# Spindle_Control.net
KiCad netlist of a schematic drawn in Altium Designer
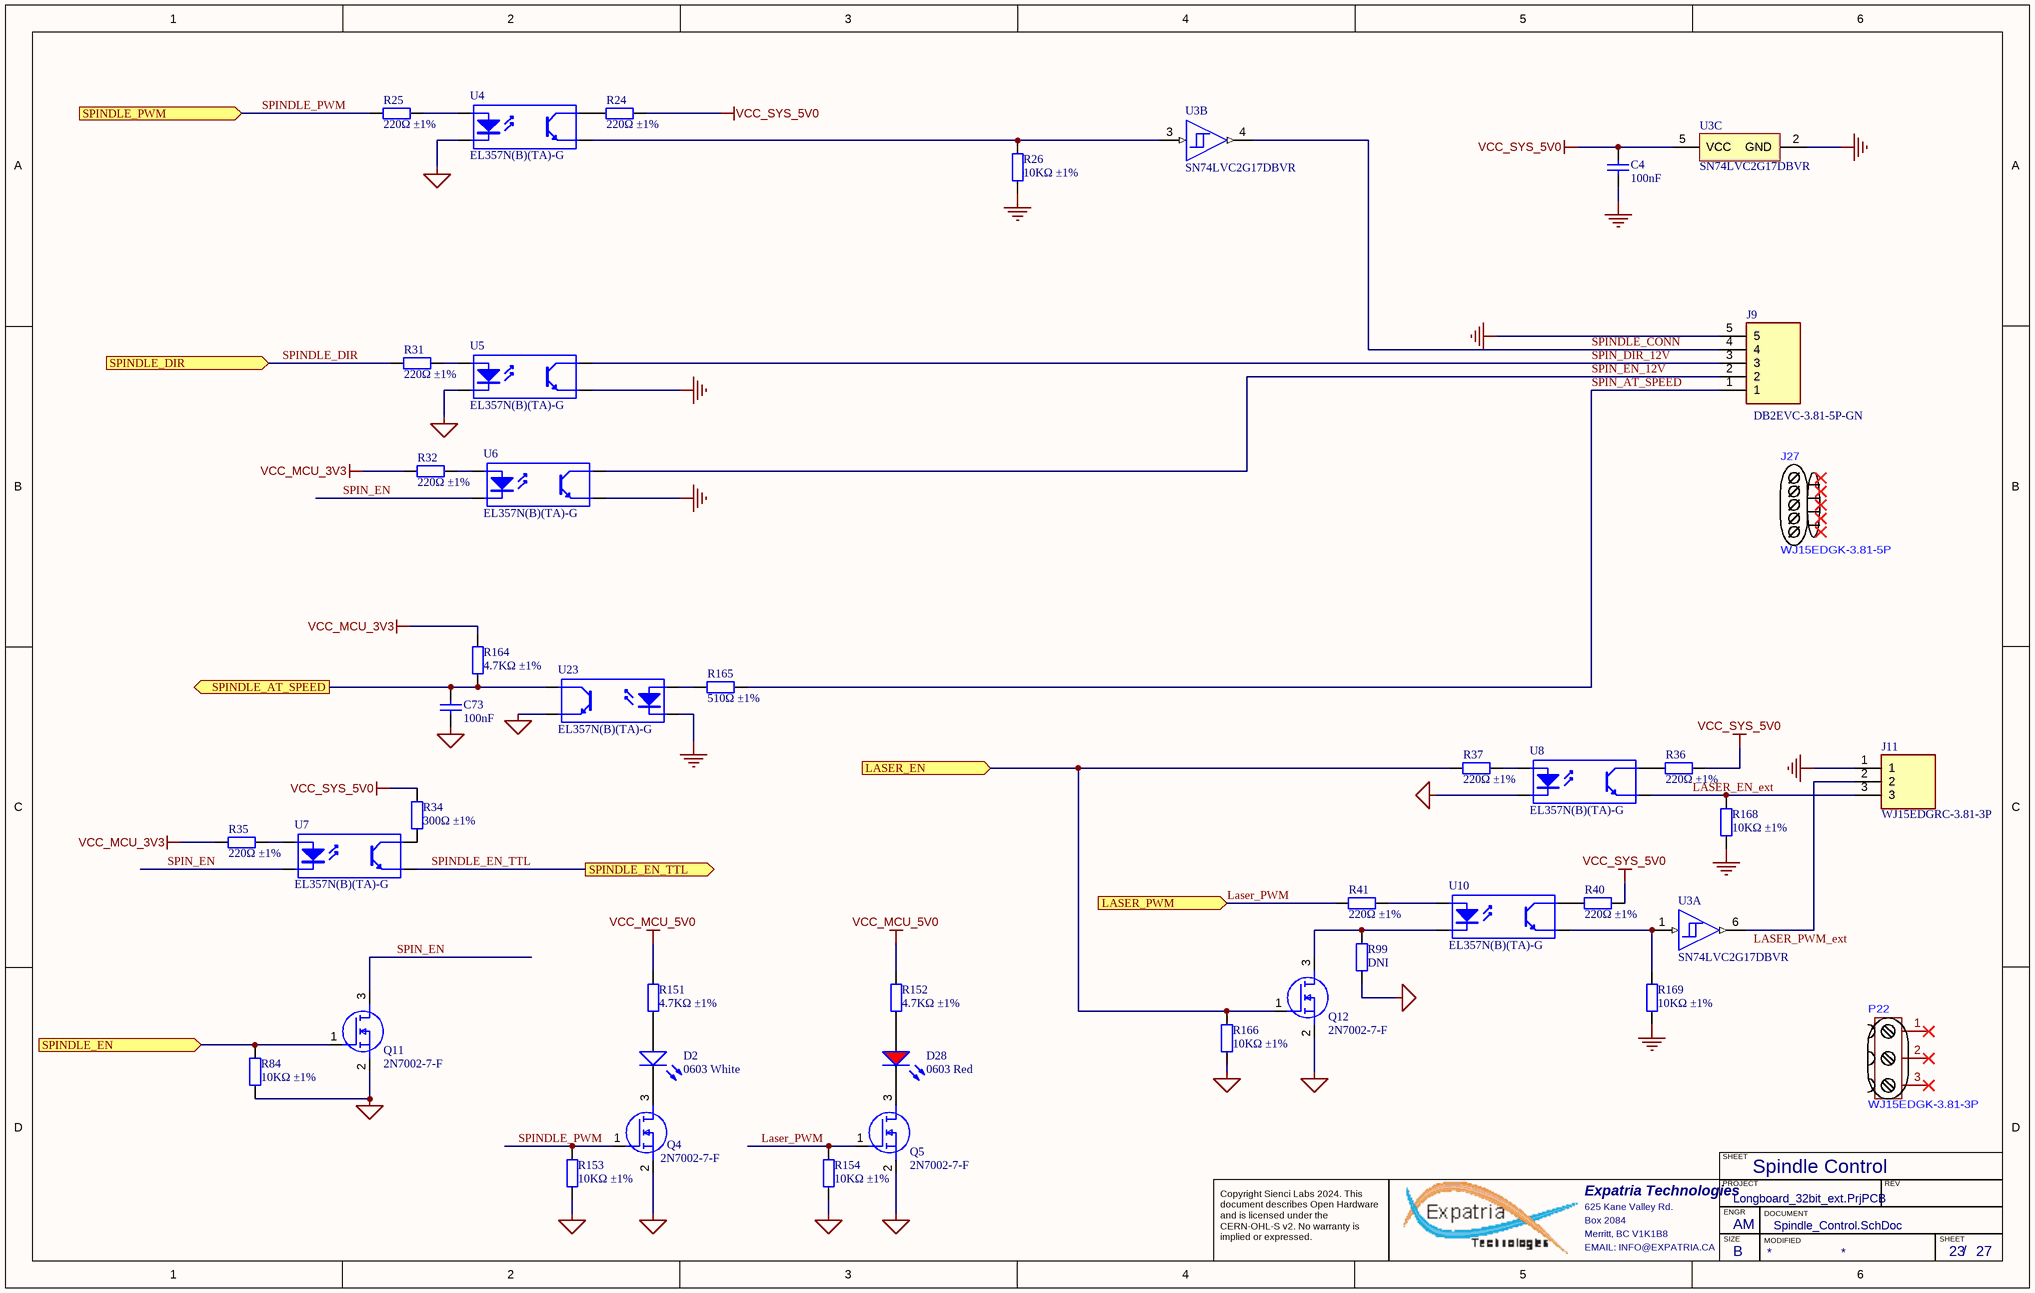
[diagram p0: Spindle_Control.SchDoc]

(export (version "E")
  (design (tool "Eeschema 10.0.6"))
  (components
    (comp (ref "C4")
      (value "100nF")
      (footprint "0603_C")
      (description "50V 100nF X7R ±10% 0603 Multilayer Ceramic Capacitors MLCC - SMD/SMT ROHS")
      (fields
        (field (name "MANUFACTURER") "YAGEO")
        (field (name "MANUFACTURER PART NUMBER") "CC0603KRX7R9BB104")
      )
      (libsource (lib "Sienci_Labs") (part "0603 100nF (104) 10% 50V"))
    )
    (comp (ref "C73")
      (value "100nF")
      (footprint "0402_C")
      (description "16V 100nF X7R ±10% 0402 Multilayer Ceramic Capacitors MLCC - SMD/SMT ROHS")
      (fields (field (name "MANUFACTURER") "Samsung Electro-Mechanics") (field (name "TOLERANCE") "10%"))
      (libsource (lib "Sienci_Labs") (part "0402 100nF (104) 10% 16V"))
    )
    (comp (ref "D2")
      (value "0603 White")
      (footprint "0603_LED_S1 - white")
      (description "White LED")
      (fields
        (field (name "MANUFACTURER PART NUMBER") "19-218/T1D-CQ2R2TY/3T")
        (field (name "MANUFACTURER") "Everlight Elec")
      )
      (libsource (lib "Sienci_Labs") (part "19-218/T1D-CQ2R2TY/3T"))
    )
    (comp (ref "D28")
      (value "0603 Red")
      (footprint "0603_LED_S1")
      (description "-40℃~+85℃ Red 0603 Light Emitting Diodes (LED) ROHS")
      (fields
        (field (name "MANUFACTURER") "Hubei KENTO Elec")
        (field (name "MANUFACTURER PART NUMBER") "KT-0603R")
      )
      (libsource (lib "Sienci_Labs") (part "KT-0603R"))
    )
    (comp (ref "J9")
      (value "DB2EVC-3.81-5P-GN")
      (footprint "CONN-TH_5P-P3.81_DB2EVC-3.81-5P")
      (description "3.81mm Green Board Edge/Receptacle-Close Push-Pull,P=3.81mm Pluggable System Terminal Block ROHS")
      (fields (field (name "MANUFACTURER") "DIBO"))
      (libsource (lib "Sienci_Labs") (part "DB2EVC-3.81-5P-GN"))
    )
    (comp (ref "J11")
      (value "WJ15EDGRC-3.81-3P")
      (footprint "SHDRRA3W85P0X381_1X3_1231X915X720P")
      (description "3.81mm Green Board Edge/Receptacle-Close Push-Pull,P=3.81mm Pluggable System Terminal Block ROHS")
      (fields (field (name "MANUFACTURER") "Ningbo Kangnex"))
      (libsource (lib "Sienci_Labs") (part "WJ15EDGRC-3.81-3P"))
    )
    (comp (ref "J27")
      (value "WJ15EDGK-3.81-5P")
      (description "3.81mm Green Plug P=3.81mm Pluggable System Terminal Block ROHS")
      (fields (field (name "MANUFACTURER") "Ningbo Kangnex Elec"))
      (libsource (lib "Sienci_Labs") (part "WJ15EDGK-3.81-5P"))
    )
    (comp (ref "P22")
      (value "WJ15EDGK-3.81-3P")
      (description "3.81mm Green Plug P=3.81mm Pluggable System Terminal Block ROHS")
      (fields (field (name "MANUFACTURER") "Ningbo"))
      (libsource (lib "Sienci_Labs") (part "WJ15EDGK-3.81-3P"))
    )
    (comp (ref "Q4")
      (value "2N7002-7-F")
      (footprint "SOT-23(SOT-23-3)")
      (description "60V 115mA 7.5Ω@5V,50mA 370mW N Channel SOT-23 MOSFETs ROHS")
      (fields (field (name "MANUFACTURER") "Diodes Inc.") (field (name "MOUSER PART NUMBER") "621-2N7002-F"))
      (libsource (lib "Sienci_Labs") (part "2N7002-7-F"))
    )
    (comp (ref "Q5")
      (value "2N7002-7-F")
      (footprint "SOT-23(SOT-23-3)")
      (description "60V 115mA 7.5Ω@5V,50mA 370mW N Channel SOT-23 MOSFETs ROHS")
      (fields (field (name "MANUFACTURER") "Diodes Inc.") (field (name "MOUSER PART NUMBER") "621-2N7002-F"))
      (libsource (lib "Sienci_Labs") (part "2N7002-7-F"))
    )
    (comp (ref "Q11")
      (value "2N7002-7-F")
      (footprint "SOT-23(SOT-23-3)")
      (description "60V 115mA 7.5Ω@5V,50mA 370mW N Channel SOT-23 MOSFETs ROHS")
      (fields (field (name "MANUFACTURER") "Diodes Inc.") (field (name "MOUSER PART NUMBER") "621-2N7002-F"))
      (libsource (lib "Sienci_Labs") (part "2N7002-7-F"))
    )
    (comp (ref "Q12")
      (value "2N7002-7-F")
      (footprint "SOT-23(SOT-23-3)")
      (description "60V 115mA 7.5Ω@5V,50mA 370mW N Channel SOT-23 MOSFETs ROHS")
      (fields (field (name "MANUFACTURER") "Diodes Inc.") (field (name "MOUSER PART NUMBER") "621-2N7002-F"))
      (libsource (lib "Sienci_Labs") (part "2N7002-7-F"))
    )
    (comp (ref "R24")
      (value "220Ω ±1%")
      (footprint "0402_R")
      (description "Chip resistor")
      (fields
        (field (name "MANUFACTURER") "Uniroyal Elec")
        (field (name "MANUFACTURER PART NUMBER") "0402WGF2200TCE")
      )
      (libsource (lib "RES") (part "0402 220R (2200) 1%"))
    )
    (comp (ref "R25")
      (value "220Ω ±1%")
      (footprint "0402_R")
      (description "Chip resistor")
      (fields
        (field (name "MANUFACTURER") "Uniroyal Elec")
        (field (name "MANUFACTURER PART NUMBER") "0402WGF2200TCE")
      )
      (libsource (lib "RES") (part "0402 220R (2200) 1%"))
    )
    (comp (ref "R26")
      (value "10KΩ ±1%")
      (footprint "0402_R")
      (description "Chip resistor")
      (fields
        (field (name "MANUFACTURER") "Uniroyal Elec")
        (field (name "MANUFACTURER PART NUMBER") "0402WGF1002TCE")
      )
      (libsource (lib "Sienci_Labs") (part "0402 10K (1002) 1%"))
    )
    (comp (ref "R31")
      (value "220Ω ±1%")
      (footprint "0402_R")
      (description "Chip resistor")
      (fields
        (field (name "MANUFACTURER") "Uniroyal Elec")
        (field (name "MANUFACTURER PART NUMBER") "0402WGF2200TCE")
      )
      (libsource (lib "RES") (part "0402 220R (2200) 1%"))
    )
    (comp (ref "R32")
      (value "220Ω ±1%")
      (footprint "0402_R")
      (description "Chip resistor")
      (fields
        (field (name "MANUFACTURER") "Uniroyal Elec")
        (field (name "MANUFACTURER PART NUMBER") "0402WGF2200TCE")
      )
      (libsource (lib "RES") (part "0402 220R (2200) 1%"))
    )
    (comp (ref "R34")
      (value "300Ω ±1%")
      (footprint "0603_R")
      (description "Chip resistor")
      (fields
        (field (name "MANUFACTURER") "Uniroyal Elec")
        (field (name "MANUFACTURER PART NUMBER") "0603WAF3000T5E")
      )
      (libsource (lib "RES") (part "0603 300R (3000) 1%"))
    )
    (comp (ref "R35")
      (value "220Ω ±1%")
      (footprint "0402_R")
      (description "Chip resistor")
      (fields
        (field (name "MANUFACTURER") "Uniroyal Elec")
        (field (name "MANUFACTURER PART NUMBER") "0402WGF2200TCE")
      )
      (libsource (lib "RES") (part "0402 220R (2200) 1%"))
    )
    (comp (ref "R36")
      (value "220Ω ±1%")
      (footprint "0402_R")
      (description "Chip resistor")
      (fields
        (field (name "MANUFACTURER") "Uniroyal Elec")
        (field (name "MANUFACTURER PART NUMBER") "0402WGF2200TCE")
      )
      (libsource (lib "RES") (part "0402 220R (2200) 1%"))
    )
    (comp (ref "R37")
      (value "220Ω ±1%")
      (footprint "0402_R")
      (description "Chip resistor")
      (fields
        (field (name "MANUFACTURER") "Uniroyal Elec")
        (field (name "MANUFACTURER PART NUMBER") "0402WGF2200TCE")
      )
      (libsource (lib "RES") (part "0402 220R (2200) 1%"))
    )
    (comp (ref "R40")
      (value "220Ω ±1%")
      (footprint "0402_R")
      (description "Chip resistor")
      (fields
        (field (name "MANUFACTURER") "Uniroyal Elec")
        (field (name "MANUFACTURER PART NUMBER") "0402WGF2200TCE")
      )
      (libsource (lib "") (part "0402 220R (2200) 1%_1"))
    )
    (comp (ref "R41")
      (value "220Ω ±1%")
      (footprint "0402_R")
      (description "Chip resistor")
      (fields
        (field (name "MANUFACTURER") "Uniroyal Elec")
        (field (name "MANUFACTURER PART NUMBER") "0402WGF2200TCE")
      )
      (libsource (lib "RES") (part "0402 220R (2200) 1%"))
    )
    (comp (ref "R84")
      (value "10KΩ ±1%")
      (footprint "0402_R")
      (description "Chip resistor")
      (fields
        (field (name "MANUFACTURER") "Uniroyal Elec")
        (field (name "MANUFACTURER PART NUMBER") "0402WGF1002TCE")
      )
      (libsource (lib "Sienci_Labs") (part "0402 10K (1002) 1%"))
    )
    (comp (ref "R99")
      (value "DNI")
      (footprint "0603_R")
      (description "Chip resistor")
      (fields
        (field (name "MANUFACTURER") "Uniroyal Elec")
        (field (name "MANUFACTURER PART NUMBER") "0603WAF0000T5E")
      )
      (libsource (lib "Sienci_Labs") (part "0603 0R (0R0) 1%"))
    )
    (comp (ref "R151")
      (value "4.7KΩ ±1%")
      (footprint "0402_R")
      (description "Chip resistor")
      (fields
        (field (name "MANUFACTURER") "Uniroyal Elec")
        (field (name "MANUFACTURER PART NUMBER") "0402WGF4701TCE")
      )
      (libsource (lib "Sienci_Labs") (part "0402 4.7K (4701) 1%"))
    )
    (comp (ref "R152")
      (value "4.7KΩ ±1%")
      (footprint "0402_R")
      (description "Chip resistor")
      (fields
        (field (name "MANUFACTURER") "Uniroyal Elec")
        (field (name "MANUFACTURER PART NUMBER") "0402WGF4701TCE")
      )
      (libsource (lib "Sienci_Labs") (part "0402 4.7K (4701) 1%"))
    )
    (comp (ref "R153")
      (value "10KΩ ±1%")
      (footprint "0402_R")
      (description "Chip resistor")
      (fields
        (field (name "MANUFACTURER") "Uniroyal Elec")
        (field (name "MANUFACTURER PART NUMBER") "0402WGF1002TCE")
      )
      (libsource (lib "Sienci_Labs") (part "0402 10K (1002) 1%"))
    )
    (comp (ref "R154")
      (value "10KΩ ±1%")
      (footprint "0402_R")
      (description "Chip resistor")
      (fields
        (field (name "MANUFACTURER") "Uniroyal Elec")
        (field (name "MANUFACTURER PART NUMBER") "0402WGF1002TCE")
      )
      (libsource (lib "Sienci_Labs") (part "0402 10K (1002) 1%"))
    )
    (comp (ref "R164")
      (value "4.7KΩ ±1%")
      (footprint "0402_R")
      (description "Chip resistor")
      (fields (field (name "MANUFACTURER") "Uniroyal Elec") (field (name "POWER") "1/16W"))
      (libsource (lib "") (part "0402 4.7K (4701) 1%_1"))
    )
    (comp (ref "R165")
      (value "510Ω ±1%")
      (footprint "0402_R")
      (description "Chip resistor")
      (fields
        (field (name "MANUFACTURER") "Uniroyal Elec")
        (field (name "MANUFACTURER PART NUMBER") "0402WGF5100TCE")
      )
      (libsource (lib "RES") (part "0402 510R (5100) 1%"))
    )
    (comp (ref "R166")
      (value "10KΩ ±1%")
      (footprint "0402_R")
      (description "Chip resistor")
      (fields
        (field (name "MANUFACTURER") "Uniroyal Elec")
        (field (name "MANUFACTURER PART NUMBER") "0402WGF1002TCE")
      )
      (libsource (lib "Sienci_Labs") (part "0402 10K (1002) 1%"))
    )
    (comp (ref "R168")
      (value "10KΩ ±1%")
      (footprint "0402_R")
      (description "Chip resistor")
      (fields
        (field (name "MANUFACTURER") "Uniroyal Elec")
        (field (name "MANUFACTURER PART NUMBER") "0402WGF1002TCE")
      )
      (libsource (lib "Sienci_Labs") (part "0402 10K (1002) 1%"))
    )
    (comp (ref "R169")
      (value "10KΩ ±1%")
      (footprint "0402_R")
      (description "Chip resistor")
      (fields
        (field (name "MANUFACTURER") "Uniroyal Elec")
        (field (name "MANUFACTURER PART NUMBER") "0402WGF1002TCE")
      )
      (libsource (lib "Sienci_Labs") (part "0402 10K (1002) 1%"))
    )
    (comp (ref "U3")
      (value "SN74LVC2G17DBVR")
      (footprint "DBV0006A_N")
      (description "Dual Schmitt-Trigger Buffer, DBV0006A, LARGE T&R")
      (fields
        (field (name "GENERIC PART NUMBER") "SN74LVC2G17")
        (field (name "MANUFACTURER") "Texas Instruments")
      )
      (libsource (lib "Altium Content Vault") (part "TI-SN74XXX2GXXX-6_A-SCHMITT"))
    )
    (comp (ref "U4")
      (value "EL357N(B)(TA)-G")
      (footprint "Miscellaneous Devices LC:SOP-4_P2.54")
      (description "Optocoupler SOP-4, EL357N(B)(TA)-G, Everlight Electronics")
      (fields (field (name "MANUFACTURER") "Everlight"))
      (libsource (lib "Sienci_Labs") (part "EL357N(B)(TA)-G_[C6649]"))
    )
    (comp (ref "U5")
      (value "EL357N(B)(TA)-G")
      (footprint "Miscellaneous Devices LC:SOP-4_P2.54")
      (description "Optocoupler SOP-4, EL357N(B)(TA)-G, Everlight Electronics")
      (fields (field (name "MANUFACTURER") "Everlight"))
      (libsource (lib "Sienci_Labs") (part "EL357N(B)(TA)-G_[C6649]"))
    )
    (comp (ref "U6")
      (value "EL357N(B)(TA)-G")
      (footprint "Miscellaneous Devices LC:SOP-4_P2.54")
      (description "Optocoupler SOP-4, EL357N(B)(TA)-G, Everlight Electronics")
      (fields (field (name "MANUFACTURER") "Everlight"))
      (libsource (lib "Sienci_Labs") (part "EL357N(B)(TA)-G_[C6649]"))
    )
    (comp (ref "U7")
      (value "EL357N(B)(TA)-G")
      (footprint "Miscellaneous Devices LC:SOP-4_P2.54")
      (description "Optocoupler SOP-4, EL357N(B)(TA)-G, Everlight Electronics")
      (fields (field (name "MANUFACTURER") "Everlight"))
      (libsource (lib "Sienci_Labs") (part "EL357N(B)(TA)-G_[C6649]"))
    )
    (comp (ref "U8")
      (value "EL357N(B)(TA)-G")
      (footprint "Miscellaneous Devices LC:SOP-4_P2.54")
      (description "Optocoupler SOP-4, EL357N(B)(TA)-G, Everlight Electronics")
      (fields (field (name "MANUFACTURER") "Everlight"))
      (libsource (lib "Sienci_Labs") (part "EL357N(B)(TA)-G_[C6649]"))
    )
    (comp (ref "U10")
      (value "EL357N(B)(TA)-G")
      (footprint "Miscellaneous Devices LC:SOP-4_P2.54")
      (description "Optocoupler SOP-4, EL357N(B)(TA)-G, Everlight Electronics")
      (fields (field (name "MANUFACTURER") "Everlight"))
      (libsource (lib "Sienci_Labs") (part "EL357N(B)(TA)-G_[C6649]"))
    )
    (comp (ref "U23")
      (value "EL357N(B)(TA)-G")
      (footprint "Miscellaneous Devices LC:SOP-4_P2.54")
      (description "Optocoupler SOP-4, EL357N(B)(TA)-G, Everlight Electronics")
      (fields (field (name "MANUFACTURER") "Everlight"))
      (libsource (lib "Sienci_Labs") (part "EL357N(B)(TA)-G_[C6649]"))
    )
  )
  (nets
    (net (code "1") (name "/LASER_EN") (class "Default")
      (node (ref "Q12") (pin "1") (pinfunction "G_1") (pintype "passive"))
      (node (ref "R166") (pin "2") (pinfunction "2_2") (pintype "passive"))
      (node (ref "R37") (pin "1") (pinfunction "1_1") (pintype "passive"))
    )
    (net (code "2") (name "/LASER_EN_ext") (class "Default")
      (node (ref "J11") (pin "3") (pinfunction "3_3") (pintype "passive"))
      (node (ref "R168") (pin "2") (pinfunction "2_2") (pintype "passive"))
      (node (ref "U8") (pin "3") (pinfunction "E_3") (pintype "passive"))
    )
    (net (code "3") (name "/LASER_PWM_ext") (class "Default")
      (node (ref "J11") (pin "2") (pinfunction "2_2") (pintype "passive"))
      (node (ref "U3") (pin "6") (pinfunction "1Y_6") (pintype "output"))
    )
    (net (code "4") (name "/Laser_PWM") (class "Default")
      (node (ref "Q5") (pin "1") (pinfunction "G_1") (pintype "passive"))
      (node (ref "R154") (pin "2") (pinfunction "2_2") (pintype "passive"))
      (node (ref "R41") (pin "1") (pinfunction "1_1") (pintype "passive"))
    )
    (net (code "5") (name "/SPINDLE_AT_SPEED") (class "Default")
      (node (ref "C73") (pin "2") (pinfunction "2_2") (pintype "passive"))
      (node (ref "R164") (pin "2") (pinfunction "2_2") (pintype "passive"))
      (node (ref "U23") (pin "4") (pinfunction "C_4") (pintype "passive"))
    )
    (net (code "6") (name "/SPINDLE_CONN") (class "Default")
      (node (ref "J9") (pin "4") (pinfunction "4_4") (pintype "passive"))
      (node (ref "U3") (pin "4") (pinfunction "2Y_4") (pintype "output"))
    )
    (net (code "7") (name "/SPINDLE_DIR") (class "Default")
      (node (ref "R31") (pin "1") (pinfunction "1_1") (pintype "passive"))
    )
    (net (code "8") (name "/SPINDLE_EN") (class "Default")
      (node (ref "Q11") (pin "1") (pinfunction "G_1") (pintype "passive"))
      (node (ref "R84") (pin "2") (pinfunction "2_2") (pintype "passive"))
    )
    (net (code "9") (name "/SPINDLE_EN_TTL") (class "Default")
      (node (ref "U7") (pin "3") (pinfunction "E_3") (pintype "passive"))
    )
    (net (code "10") (name "/SPINDLE_PWM") (class "Default")
      (node (ref "Q4") (pin "1") (pinfunction "G_1") (pintype "passive"))
      (node (ref "R153") (pin "2") (pinfunction "2_2") (pintype "passive"))
      (node (ref "R25") (pin "1") (pinfunction "1_1") (pintype "passive"))
    )
    (net (code "11") (name "/SPIN_AT_SPEED") (class "Default")
      (node (ref "J9") (pin "1") (pinfunction "1_1") (pintype "passive"))
      (node (ref "R165") (pin "1") (pinfunction "1_1") (pintype "passive"))
    )
    (net (code "12") (name "/SPIN_DIR_12V") (class "Default")
      (node (ref "J9") (pin "3") (pinfunction "3_3") (pintype "passive"))
      (node (ref "U5") (pin "4") (pinfunction "C_4") (pintype "passive"))
    )
    (net (code "13") (name "/SPIN_EN") (class "Default")
      (node (ref "Q11") (pin "3") (pinfunction "D_3") (pintype "passive"))
      (node (ref "U6") (pin "2") (pinfunction "K_2") (pintype "passive"))
      (node (ref "U7") (pin "2") (pinfunction "K_2") (pintype "passive"))
    )
    (net (code "14") (name "/SPIN_EN_12V") (class "Default")
      (node (ref "J9") (pin "2") (pinfunction "2_2") (pintype "passive"))
      (node (ref "U6") (pin "4") (pinfunction "C_4") (pintype "passive"))
    )
    (net (code "15") (name "GND") (class "Default")
      (node (ref "C4") (pin "1") (pinfunction "1_1") (pintype "passive"))
      (node (ref "J11") (pin "1") (pinfunction "1_1") (pintype "passive"))
      (node (ref "J9") (pin "5") (pinfunction "5_5") (pintype "passive"))
      (node (ref "R168") (pin "1") (pinfunction "1_1") (pintype "passive"))
      (node (ref "R169") (pin "1") (pinfunction "1_1") (pintype "passive"))
      (node (ref "R26") (pin "1") (pinfunction "1_1") (pintype "passive"))
      (node (ref "U23") (pin "2") (pinfunction "K_2") (pintype "passive"))
      (node (ref "U3") (pin "2") (pinfunction "GND_2") (pintype "power_in"))
      (node (ref "U5") (pin "3") (pinfunction "E_3") (pintype "passive"))
      (node (ref "U6") (pin "3") (pinfunction "E_3") (pintype "passive"))
    )
    (net (code "16") (name "MCU_GND") (class "Default")
      (node (ref "C73") (pin "1") (pinfunction "1_1") (pintype "passive"))
      (node (ref "Q11") (pin "2") (pinfunction "S_2") (pintype "passive"))
      (node (ref "Q12") (pin "2") (pinfunction "S_2") (pintype "passive"))
      (node (ref "Q4") (pin "2") (pinfunction "S_2") (pintype "passive"))
      (node (ref "Q5") (pin "2") (pinfunction "S_2") (pintype "passive"))
      (node (ref "R153") (pin "1") (pinfunction "1_1") (pintype "passive"))
      (node (ref "R154") (pin "1") (pinfunction "1_1") (pintype "passive"))
      (node (ref "R166") (pin "1") (pinfunction "1_1") (pintype "passive"))
      (node (ref "R84") (pin "1") (pinfunction "1_1") (pintype "passive"))
      (node (ref "R99") (pin "2") (pinfunction "2_2") (pintype "passive"))
      (node (ref "U23") (pin "3") (pinfunction "E_3") (pintype "passive"))
      (node (ref "U4") (pin "2") (pinfunction "K_2") (pintype "passive"))
      (node (ref "U5") (pin "2") (pinfunction "K_2") (pintype "passive"))
      (node (ref "U8") (pin "2") (pinfunction "K_2") (pintype "passive"))
    )
    (net (code "17") (name "Net-(D2-PadA)") (class "Default")
      (node (ref "D2") (pin "A") (pinfunction "A_A") (pintype "passive"))
      (node (ref "R151") (pin "1") (pinfunction "1_1") (pintype "passive"))
    )
    (net (code "18") (name "Net-(D28-PadA)") (class "Default")
      (node (ref "D28") (pin "A") (pinfunction "A_A") (pintype "passive"))
      (node (ref "R152") (pin "1") (pinfunction "1_1") (pintype "passive"))
    )
    (net (code "19") (name "Net-(Q4-D)") (class "Default")
      (node (ref "D2") (pin "K") (pinfunction "K_K") (pintype "passive"))
      (node (ref "Q4") (pin "3") (pinfunction "D_3") (pintype "passive"))
    )
    (net (code "20") (name "Net-(Q5-D)") (class "Default")
      (node (ref "D28") (pin "K") (pinfunction "K_K") (pintype "passive"))
      (node (ref "Q5") (pin "3") (pinfunction "D_3") (pintype "passive"))
    )
    (net (code "21") (name "Net-(Q12-D)") (class "Default")
      (node (ref "Q12") (pin "3") (pinfunction "D_3") (pintype "passive"))
      (node (ref "R99") (pin "1") (pinfunction "1_1") (pintype "passive"))
      (node (ref "U10") (pin "2") (pinfunction "K_2") (pintype "passive"))
    )
    (net (code "22") (name "Net-(U3B-2A)") (class "Default")
      (node (ref "R26") (pin "2") (pinfunction "2_2") (pintype "passive"))
      (node (ref "U3") (pin "3") (pinfunction "2A_3") (pintype "input"))
      (node (ref "U4") (pin "3") (pinfunction "E_3") (pintype "passive"))
    )
    (net (code "23") (name "Net-(U4-A)") (class "Default")
      (node (ref "R25") (pin "2") (pinfunction "2_2") (pintype "passive"))
      (node (ref "U4") (pin "1") (pinfunction "A_1") (pintype "passive"))
    )
    (net (code "24") (name "Net-(U4-C)") (class "Default")
      (node (ref "R24") (pin "1") (pinfunction "1_1") (pintype "passive"))
      (node (ref "U4") (pin "4") (pinfunction "C_4") (pintype "passive"))
    )
    (net (code "25") (name "Net-(U5-A)") (class "Default")
      (node (ref "R31") (pin "2") (pinfunction "2_2") (pintype "passive"))
      (node (ref "U5") (pin "1") (pinfunction "A_1") (pintype "passive"))
    )
    (net (code "26") (name "Net-(U6-A)") (class "Default")
      (node (ref "R32") (pin "2") (pinfunction "2_2") (pintype "passive"))
      (node (ref "U6") (pin "1") (pinfunction "A_1") (pintype "passive"))
    )
    (net (code "27") (name "Net-(U7-A)") (class "Default")
      (node (ref "R35") (pin "2") (pinfunction "2_2") (pintype "passive"))
      (node (ref "U7") (pin "1") (pinfunction "A_1") (pintype "passive"))
    )
    (net (code "28") (name "Net-(U7-C)") (class "Default")
      (node (ref "R34") (pin "2") (pinfunction "2_2") (pintype "passive"))
      (node (ref "U7") (pin "4") (pinfunction "C_4") (pintype "passive"))
    )
    (net (code "29") (name "Net-(U8-A)") (class "Default")
      (node (ref "R37") (pin "2") (pinfunction "2_2") (pintype "passive"))
      (node (ref "U8") (pin "1") (pinfunction "A_1") (pintype "passive"))
    )
    (net (code "30") (name "Net-(U8-C)") (class "Default")
      (node (ref "R36") (pin "1") (pinfunction "1_1") (pintype "passive"))
      (node (ref "U8") (pin "4") (pinfunction "C_4") (pintype "passive"))
    )
    (net (code "31") (name "Net-(U10-A)") (class "Default")
      (node (ref "R41") (pin "2") (pinfunction "2_2") (pintype "passive"))
      (node (ref "U10") (pin "1") (pinfunction "A_1") (pintype "passive"))
    )
    (net (code "32") (name "Net-(U10-C)") (class "Default")
      (node (ref "R40") (pin "2") (pinfunction "2_2") (pintype "passive"))
      (node (ref "U10") (pin "4") (pinfunction "C_4") (pintype "passive"))
    )
    (net (code "33") (name "Net-(U10-E)") (class "Default")
      (node (ref "R169") (pin "2") (pinfunction "2_2") (pintype "passive"))
      (node (ref "U10") (pin "3") (pinfunction "E_3") (pintype "passive"))
      (node (ref "U3") (pin "1") (pinfunction "1A_1") (pintype "input"))
    )
    (net (code "34") (name "Net-(U23-A)") (class "Default")
      (node (ref "R165") (pin "2") (pinfunction "2_2") (pintype "passive"))
      (node (ref "U23") (pin "1") (pinfunction "A_1") (pintype "passive"))
    )
    (net (code "35") (name "VCC_MCU_3V3") (class "Default")
      (node (ref "R164") (pin "1") (pinfunction "1_1") (pintype "passive"))
      (node (ref "R32") (pin "1") (pinfunction "1_1") (pintype "passive"))
      (node (ref "R35") (pin "1") (pinfunction "1_1") (pintype "passive"))
    )
    (net (code "36") (name "VCC_MCU_5V0") (class "Default")
      (node (ref "R151") (pin "2") (pinfunction "2_2") (pintype "passive"))
      (node (ref "R152") (pin "2") (pinfunction "2_2") (pintype "passive"))
    )
    (net (code "37") (name "VCC_SYS_5V0") (class "Default")
      (node (ref "C4") (pin "2") (pinfunction "2_2") (pintype "passive"))
      (node (ref "R24") (pin "2") (pinfunction "2_2") (pintype "passive"))
      (node (ref "R34") (pin "1") (pinfunction "1_1") (pintype "passive"))
      (node (ref "R36") (pin "2") (pinfunction "2_2") (pintype "passive"))
      (node (ref "R40") (pin "1") (pinfunction "1_1") (pintype "passive"))
      (node (ref "U3") (pin "5") (pinfunction "VCC_5") (pintype "power_in"))
    )
    (net (code "38") (name "unconnected-(P22-Pad1)") (class "Default")
      (node (ref "P22") (pin "1") (pinfunction "1_1") (pintype "passive+no_connect"))
    )
    (net (code "39") (name "unconnected-(P22-Pad2)") (class "Default")
      (node (ref "P22") (pin "2") (pinfunction "2_2") (pintype "passive+no_connect"))
    )
    (net (code "40") (name "unconnected-(P22-Pad3)") (class "Default")
      (node (ref "P22") (pin "3") (pinfunction "3_3") (pintype "passive+no_connect"))
    )
  )
)
